# amp_soha.net
KiCad netlist of a schematic drawn in EAGLE
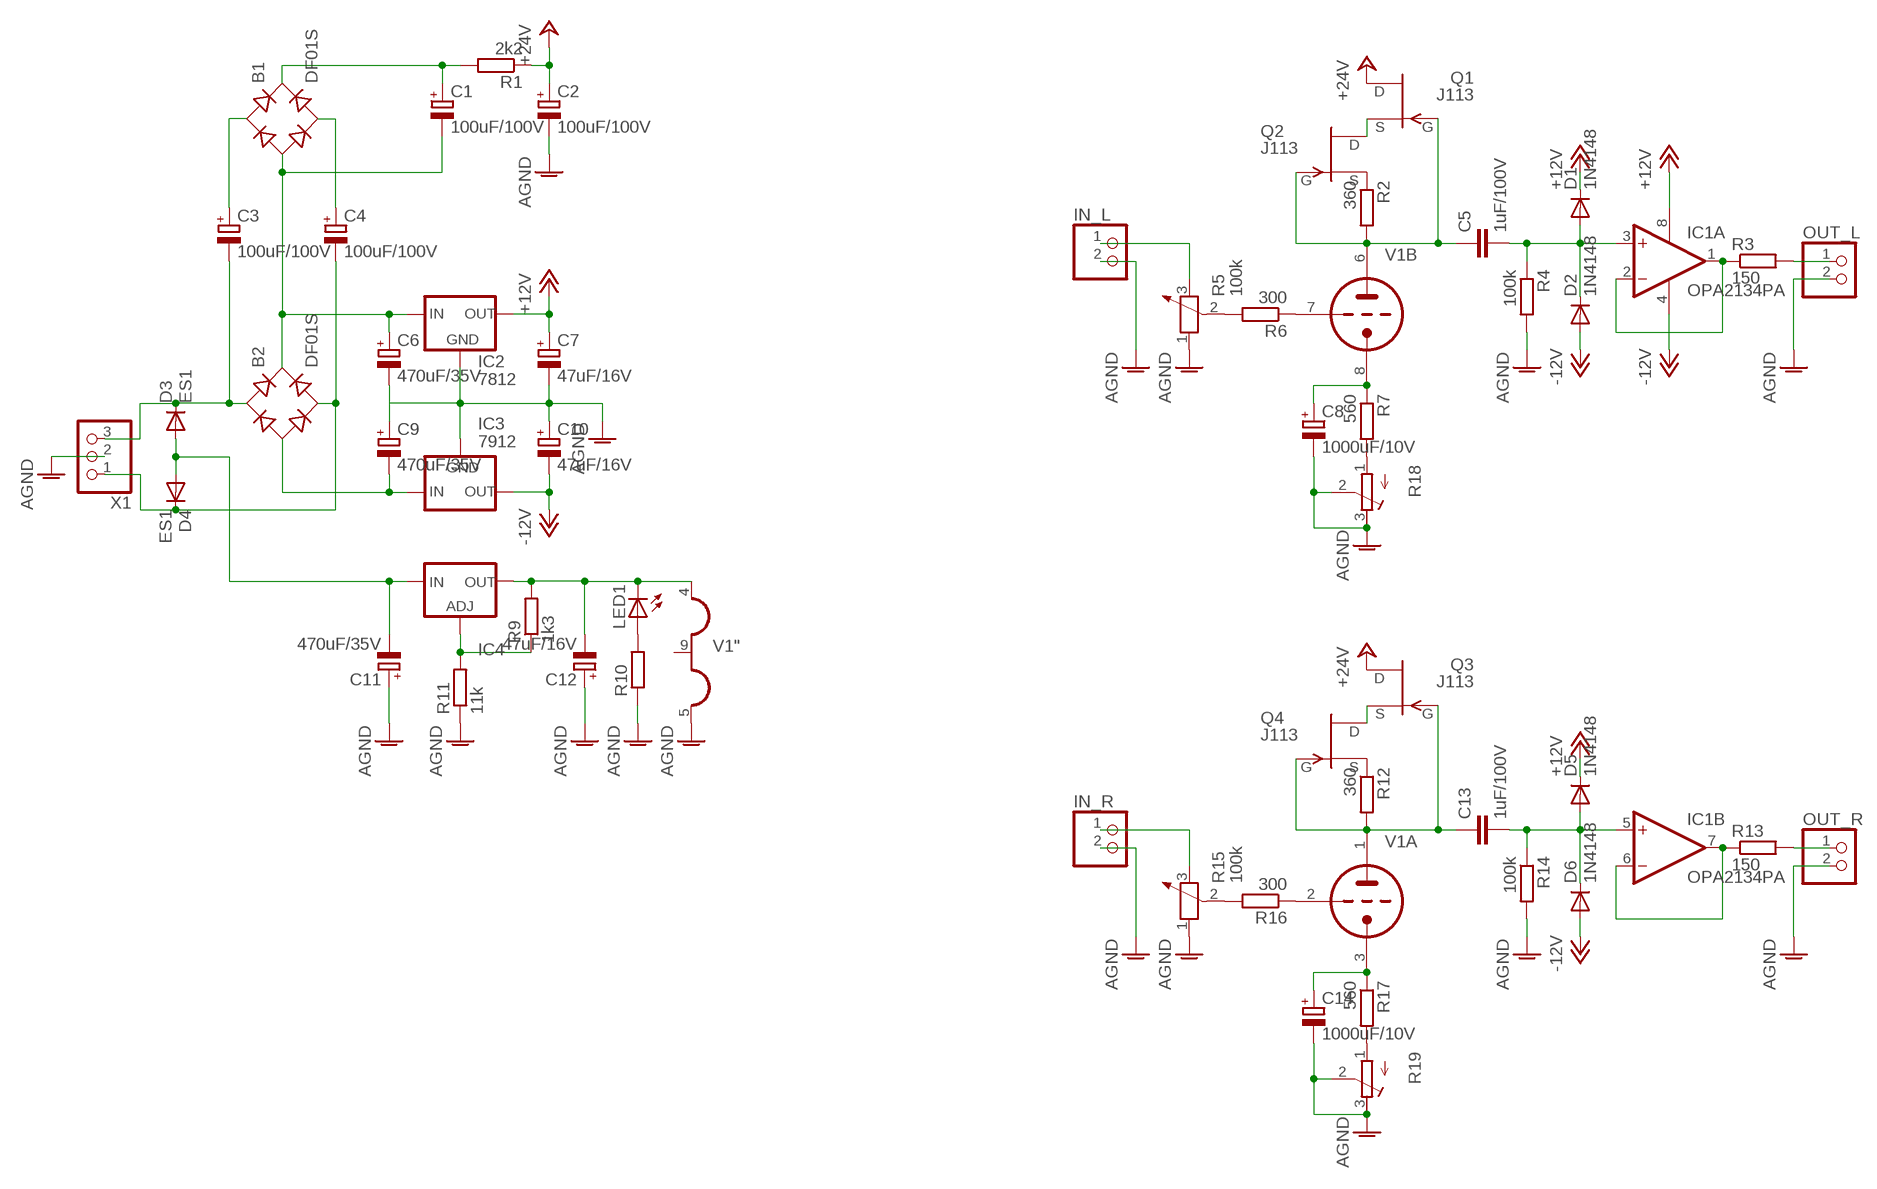
[diagram p0: schematic, sheet 1]

(export (version "E")
  (design (tool "Eeschema 10.0.6"))
  (components
    (comp (ref "B1")
      (value "DF01S")
      (footprint "eagle-import:DFS")
      (libsource (lib "eagle-import") (part "DFS01"))
    )
    (comp (ref "B2")
      (value "DF01S")
      (footprint "eagle-import:DFS")
      (libsource (lib "eagle-import") (part "DFS01"))
    )
    (comp (ref "C1")
      (value "100uF/100V")
      (footprint "eagle-import:E5-10,5")
      (libsource (lib "eagle-import") (part "CPOL-EUE5-10,5"))
    )
    (comp (ref "C2")
      (value "100uF/100V")
      (footprint "eagle-import:E5-10,5")
      (libsource (lib "eagle-import") (part "CPOL-EUE5-10,5"))
    )
    (comp (ref "C3")
      (value "100uF/100V")
      (footprint "eagle-import:E5-10,5")
      (libsource (lib "eagle-import") (part "CPOL-EUE5-10,5"))
    )
    (comp (ref "C4")
      (value "100uF/100V")
      (footprint "eagle-import:E5-10,5")
      (libsource (lib "eagle-import") (part "CPOL-EUE5-10,5"))
    )
    (comp (ref "C5")
      (value "1uF/100V")
      (footprint "eagle-import:C150-072X183")
      (libsource (lib "eagle-import") (part "C-EU150-072X183"))
    )
    (comp (ref "C6")
      (value "470uF/35V")
      (footprint "eagle-import:E5-10,5")
      (libsource (lib "eagle-import") (part "CPOL-EUE5-10,5"))
    )
    (comp (ref "C7")
      (value "47uF/16V")
      (footprint "eagle-import:E2,5-6")
      (libsource (lib "eagle-import") (part "CPOL-EUE2.5-6"))
    )
    (comp (ref "C8")
      (value "1000uF/10V")
      (footprint "eagle-import:E5-10,5")
      (libsource (lib "eagle-import") (part "CPOL-EUE5-10,5"))
    )
    (comp (ref "C9")
      (value "470uF/35V")
      (footprint "eagle-import:E5-10,5")
      (libsource (lib "eagle-import") (part "CPOL-EUE5-10,5"))
    )
    (comp (ref "C10")
      (value "47uF/16V")
      (footprint "eagle-import:E2,5-6")
      (libsource (lib "eagle-import") (part "CPOL-EUE2.5-6"))
    )
    (comp (ref "C11")
      (value "470uF/35V")
      (footprint "eagle-import:E5-10,5")
      (libsource (lib "eagle-import") (part "CPOL-EUE5-10,5"))
    )
    (comp (ref "C12")
      (value "47uF/16V")
      (footprint "eagle-import:E2,5-6")
      (libsource (lib "eagle-import") (part "CPOL-EUE2.5-6"))
    )
    (comp (ref "C13")
      (value "1uF/100V")
      (footprint "eagle-import:C150-072X183")
      (libsource (lib "eagle-import") (part "C-EU150-072X183"))
    )
    (comp (ref "C14")
      (value "1000uF/10V")
      (footprint "eagle-import:E5-10,5")
      (libsource (lib "eagle-import") (part "CPOL-EUE5-10,5"))
    )
    (comp (ref "D1")
      (value "1N4148")
      (footprint "eagle-import:D0805")
      (libsource (lib "eagle-import") (part "1N4148"))
    )
    (comp (ref "D2")
      (value "1N4148")
      (footprint "eagle-import:D0805")
      (libsource (lib "eagle-import") (part "1N4148"))
    )
    (comp (ref "D3")
      (value "ES1")
      (footprint "eagle-import:DO-214AC")
      (libsource (lib "eagle-import") (part "ES1"))
    )
    (comp (ref "D4")
      (value "ES1")
      (footprint "eagle-import:DO-214AC")
      (libsource (lib "eagle-import") (part "ES1"))
    )
    (comp (ref "D5")
      (value "1N4148")
      (footprint "eagle-import:D0805")
      (libsource (lib "eagle-import") (part "1N4148"))
    )
    (comp (ref "D6")
      (value "1N4148")
      (footprint "eagle-import:D0805")
      (libsource (lib "eagle-import") (part "1N4148"))
    )
    (comp (ref "IC1")
      (value "OPA2134PA")
      (footprint "eagle-import:DIL08")
      (libsource (lib "eagle-import") (part "OPA2PA134"))
    )
    (comp (ref "IC2")
      (value "7812")
      (footprint "eagle-import:78XXS")
      (libsource (lib "eagle-import") (part "78XXTO-220"))
    )
    (comp (ref "IC3")
      (value "7912")
      (footprint "eagle-import:79XXS")
      (libsource (lib "eagle-import") (part "79XXTO-220"))
    )
    (comp (ref "IC4")
      (value "LM337TS")
      (footprint "eagle-import:337TS")
      (libsource (lib "eagle-import") (part "LM337TS"))
    )
    (comp (ref "IN_L")
      (value "PINHD-1X2")
      (footprint "eagle-import:1X02")
      (libsource (lib "eagle-import") (part "PINHD-1X2"))
    )
    (comp (ref "IN_R")
      (value "PINHD-1X2")
      (footprint "eagle-import:1X02")
      (libsource (lib "eagle-import") (part "PINHD-1X2"))
    )
    (comp (ref "LED1")
      (value "LED5MM")
      (footprint "eagle-import:LED5MM")
      (libsource (lib "eagle-import") (part "LED5MM"))
    )
    (comp (ref "OUT_L")
      (value "PINHD-1X2")
      (footprint "eagle-import:1X02")
      (libsource (lib "eagle-import") (part "PINHD-1X2"))
    )
    (comp (ref "OUT_R")
      (value "PINHD-1X2")
      (footprint "eagle-import:1X02")
      (libsource (lib "eagle-import") (part "PINHD-1X2"))
    )
    (comp (ref "Q1")
      (value "J113")
      (footprint "eagle-import:TO92")
      (libsource (lib "eagle-import") (part "J113"))
    )
    (comp (ref "Q2")
      (value "J113")
      (footprint "eagle-import:TO92")
      (libsource (lib "eagle-import") (part "J113"))
    )
    (comp (ref "Q3")
      (value "J113")
      (footprint "eagle-import:TO92")
      (libsource (lib "eagle-import") (part "J113"))
    )
    (comp (ref "Q4")
      (value "J113")
      (footprint "eagle-import:TO92")
      (libsource (lib "eagle-import") (part "J113"))
    )
    (comp (ref "R1")
      (value "2k2")
      (footprint "eagle-import:R0805")
      (libsource (lib "eagle-import") (part "R-EU_"))
    )
    (comp (ref "R2")
      (value "360")
      (footprint "eagle-import:R0805")
      (libsource (lib "eagle-import") (part "R-EU_"))
    )
    (comp (ref "R3")
      (value "150")
      (footprint "eagle-import:R0805")
      (libsource (lib "eagle-import") (part "R-EU_"))
    )
    (comp (ref "R4")
      (value "100k")
      (footprint "eagle-import:R0805")
      (libsource (lib "eagle-import") (part "R-EU_"))
    )
    (comp (ref "R5")
      (value "100k")
      (footprint "eagle-import:1X03")
      (libsource (lib "eagle-import") (part "POTENTIOMETER_"))
    )
    (comp (ref "R6")
      (value "300")
      (footprint "eagle-import:R0805")
      (libsource (lib "eagle-import") (part "R-EU_"))
    )
    (comp (ref "R7")
      (value "560")
      (footprint "eagle-import:R0805")
      (libsource (lib "eagle-import") (part "R-EU_"))
    )
    (comp (ref "R9")
      (value "1k3")
      (footprint "eagle-import:R0805")
      (libsource (lib "eagle-import") (part "R-EU_"))
    )
    (comp (ref "R10")
      (value "R-EU_")
      (footprint "eagle-import:R0805")
      (libsource (lib "eagle-import") (part "R-EU_"))
    )
    (comp (ref "R11")
      (value "11k")
      (footprint "eagle-import:R0805")
      (libsource (lib "eagle-import") (part "R-EU_"))
    )
    (comp (ref "R12")
      (value "360")
      (footprint "eagle-import:R0805")
      (libsource (lib "eagle-import") (part "R-EU_"))
    )
    (comp (ref "R13")
      (value "150")
      (footprint "eagle-import:R0805")
      (libsource (lib "eagle-import") (part "R-EU_"))
    )
    (comp (ref "R14")
      (value "100k")
      (footprint "eagle-import:R0805")
      (libsource (lib "eagle-import") (part "R-EU_"))
    )
    (comp (ref "R15")
      (value "100k")
      (footprint "eagle-import:1X03")
      (libsource (lib "eagle-import") (part "POTENTIOMETER_"))
    )
    (comp (ref "R16")
      (value "300")
      (footprint "eagle-import:R0805")
      (libsource (lib "eagle-import") (part "R-EU_"))
    )
    (comp (ref "R17")
      (value "560")
      (footprint "eagle-import:R0805")
      (libsource (lib "eagle-import") (part "R-EU_"))
    )
    (comp (ref "R18")
      (value "RTRIM329Y")
      (footprint "eagle-import:RTRIM3296Y")
      (libsource (lib "eagle-import") (part "RTRIM329Y"))
    )
    (comp (ref "R19")
      (value "RTRIM329Y")
      (footprint "eagle-import:RTRIM3296Y")
      (libsource (lib "eagle-import") (part "RTRIM329Y"))
    )
    (comp (ref "V1")
      (value "12AU7-P")
      (footprint "eagle-import:NOVAL")
      (libsource (lib "eagle-import") (part "12AU7-P"))
    )
    (comp (ref "X1")
      (value "W237-103")
      (footprint "eagle-import:W237-103")
      (libsource (lib "eagle-import") (part "W237-103"))
    )
  )
  (nets
    (net (code "1") (name "+12V") (class "Default")
      (node (ref "C7") (pin "+") (pinfunction "+_+") (pintype "passive"))
      (node (ref "D1") (pin "K") (pinfunction "C_K") (pintype "passive"))
      (node (ref "D5") (pin "K") (pinfunction "C_K") (pintype "passive"))
      (node (ref "IC1") (pin "8") (pinfunction "V+_8") (pintype "power_in"))
      (node (ref "IC2") (pin "OUT") (pinfunction "OUT_OUT") (pintype "passive"))
    )
    (net (code "2") (name "+24V") (class "Default")
      (node (ref "C2") (pin "+") (pinfunction "+_+") (pintype "passive"))
      (node (ref "Q1") (pin "3") (pinfunction "D_3") (pintype "passive"))
      (node (ref "Q3") (pin "3") (pinfunction "D_3") (pintype "passive"))
      (node (ref "R1") (pin "1") (pinfunction "1_1") (pintype "passive"))
    )
    (net (code "3") (name "-12V") (class "Default")
      (node (ref "C10") (pin "-") (pinfunction "-_-") (pintype "passive"))
      (node (ref "D2") (pin "A") (pinfunction "A_A") (pintype "passive"))
      (node (ref "D6") (pin "A") (pinfunction "A_A") (pintype "passive"))
      (node (ref "IC1") (pin "4") (pinfunction "V-_4") (pintype "power_in"))
      (node (ref "IC3") (pin "OUT") (pinfunction "OUT_OUT") (pintype "passive"))
    )
    (net (code "4") (name "AGND") (class "Default")
      (node (ref "C10") (pin "+") (pinfunction "+_+") (pintype "passive"))
      (node (ref "C11") (pin "+") (pinfunction "+_+") (pintype "passive"))
      (node (ref "C12") (pin "+") (pinfunction "+_+") (pintype "passive"))
      (node (ref "C14") (pin "-") (pinfunction "-_-") (pintype "passive"))
      (node (ref "C2") (pin "-") (pinfunction "-_-") (pintype "passive"))
      (node (ref "C6") (pin "-") (pinfunction "-_-") (pintype "passive"))
      (node (ref "C7") (pin "-") (pinfunction "-_-") (pintype "passive"))
      (node (ref "C8") (pin "-") (pinfunction "-_-") (pintype "passive"))
      (node (ref "C9") (pin "+") (pinfunction "+_+") (pintype "passive"))
      (node (ref "IC2") (pin "GND") (pinfunction "GND_GND") (pintype "input"))
      (node (ref "IC3") (pin "GND") (pinfunction "GND_GND") (pintype "input"))
      (node (ref "IN_L") (pin "2") (pinfunction "2_2") (pintype "passive"))
      (node (ref "IN_R") (pin "2") (pinfunction "2_2") (pintype "passive"))
      (node (ref "OUT_L") (pin "2") (pinfunction "2_2") (pintype "passive"))
      (node (ref "OUT_R") (pin "2") (pinfunction "2_2") (pintype "passive"))
      (node (ref "R10") (pin "1") (pinfunction "1_1") (pintype "passive"))
      (node (ref "R11") (pin "1") (pinfunction "1_1") (pintype "passive"))
      (node (ref "R14") (pin "2") (pinfunction "2_2") (pintype "passive"))
      (node (ref "R15") (pin "1") (pinfunction "1_1") (pintype "passive"))
      (node (ref "R18") (pin "2") (pinfunction "S_2") (pintype "passive"))
      (node (ref "R18") (pin "3") (pinfunction "E_3") (pintype "passive"))
      (node (ref "R19") (pin "2") (pinfunction "S_2") (pintype "passive"))
      (node (ref "R19") (pin "3") (pinfunction "E_3") (pintype "passive"))
      (node (ref "R4") (pin "2") (pinfunction "2_2") (pintype "passive"))
      (node (ref "R5") (pin "1") (pinfunction "1_1") (pintype "passive"))
      (node (ref "V1") (pin "5") (pinfunction "H3_5") (pintype "passive"))
      (node (ref "X1") (pin "2") (pinfunction "2_2") (pintype "passive"))
    )
    (net (code "5") (name "Net-(B1-Pad+)") (class "Default")
      (node (ref "B1") (pin "+") (pinfunction "+_+") (pintype "passive"))
      (node (ref "C1") (pin "+") (pinfunction "+_+") (pintype "passive"))
      (node (ref "R1") (pin "2") (pinfunction "2_2") (pintype "passive"))
    )
    (net (code "6") (name "Net-(B1-Pad-)") (class "Default")
      (node (ref "B1") (pin "-") (pinfunction "-_-") (pintype "passive"))
      (node (ref "B2") (pin "+") (pinfunction "+_+") (pintype "passive"))
      (node (ref "C1") (pin "-") (pinfunction "-_-") (pintype "passive"))
      (node (ref "C6") (pin "+") (pinfunction "+_+") (pintype "passive"))
      (node (ref "IC2") (pin "IN") (pinfunction "IN_IN") (pintype "input"))
    )
    (net (code "7") (name "Net-(B1-PadAC1)") (class "Default")
      (node (ref "B1") (pin "AC1") (pinfunction "AC1_AC1") (pintype "passive"))
      (node (ref "C3") (pin "+") (pinfunction "+_+") (pintype "passive"))
    )
    (net (code "8") (name "Net-(B1-PadAC2)") (class "Default")
      (node (ref "B1") (pin "AC2") (pinfunction "AC2_AC2") (pintype "passive"))
      (node (ref "C4") (pin "+") (pinfunction "+_+") (pintype "passive"))
    )
    (net (code "9") (name "Net-(B2-Pad-)") (class "Default")
      (node (ref "B2") (pin "-") (pinfunction "-_-") (pintype "passive"))
      (node (ref "C9") (pin "-") (pinfunction "-_-") (pintype "passive"))
      (node (ref "IC3") (pin "IN") (pinfunction "IN_IN") (pintype "input"))
    )
    (net (code "10") (name "Net-(B2-PadAC1)") (class "Default")
      (node (ref "B2") (pin "AC1") (pinfunction "AC1_AC1") (pintype "passive"))
      (node (ref "C3") (pin "-") (pinfunction "-_-") (pintype "passive"))
      (node (ref "D3") (pin "C") (pinfunction "C_C") (pintype "passive"))
      (node (ref "X1") (pin "3") (pinfunction "3_3") (pintype "passive"))
    )
    (net (code "11") (name "Net-(B2-PadAC2)") (class "Default")
      (node (ref "B2") (pin "AC2") (pinfunction "AC2_AC2") (pintype "passive"))
      (node (ref "C4") (pin "-") (pinfunction "-_-") (pintype "passive"))
      (node (ref "D4") (pin "C") (pinfunction "C_C") (pintype "passive"))
      (node (ref "X1") (pin "1") (pinfunction "1_1") (pintype "passive"))
    )
    (net (code "12") (name "Net-(D2-C)") (class "Default")
      (node (ref "C5") (pin "2") (pinfunction "2_2") (pintype "passive"))
      (node (ref "D1") (pin "A") (pinfunction "A_A") (pintype "passive"))
      (node (ref "D2") (pin "K") (pinfunction "C_K") (pintype "passive"))
      (node (ref "IC1") (pin "3") (pinfunction "+IN_3") (pintype "input"))
      (node (ref "R4") (pin "1") (pinfunction "1_1") (pintype "passive"))
    )
    (net (code "13") (name "Net-(D6-C)") (class "Default")
      (node (ref "C13") (pin "2") (pinfunction "2_2") (pintype "passive"))
      (node (ref "D5") (pin "A") (pinfunction "A_A") (pintype "passive"))
      (node (ref "D6") (pin "K") (pinfunction "C_K") (pintype "passive"))
      (node (ref "IC1") (pin "5") (pinfunction "+IN_5") (pintype "input"))
      (node (ref "R14") (pin "1") (pinfunction "1_1") (pintype "passive"))
    )
    (net (code "14") (name "Net-(IC1A--IN)") (class "Default")
      (node (ref "IC1") (pin "1") (pinfunction "OUT_1") (pintype "output"))
      (node (ref "IC1") (pin "2") (pinfunction "-IN_2") (pintype "input"))
      (node (ref "R3") (pin "1") (pinfunction "1_1") (pintype "passive"))
    )
    (net (code "15") (name "Net-(IC1B--IN)") (class "Default")
      (node (ref "IC1") (pin "6") (pinfunction "-IN_6") (pintype "input"))
      (node (ref "IC1") (pin "7") (pinfunction "OUT_7") (pintype "output"))
      (node (ref "R13") (pin "1") (pinfunction "1_1") (pintype "passive"))
    )
    (net (code "16") (name "Net-(IC4-ADJ)") (class "Default")
      (node (ref "IC4") (pin "1") (pinfunction "ADJ_1") (pintype "input"))
      (node (ref "R11") (pin "2") (pinfunction "2_2") (pintype "passive"))
      (node (ref "R9") (pin "1") (pinfunction "1_1") (pintype "passive"))
    )
    (net (code "17") (name "Net-(IC4-IN)") (class "Default")
      (node (ref "C11") (pin "-") (pinfunction "-_-") (pintype "passive"))
      (node (ref "D3") (pin "A") (pinfunction "A_A") (pintype "passive"))
      (node (ref "D4") (pin "A") (pinfunction "A_A") (pintype "passive"))
      (node (ref "IC4") (pin "2") (pinfunction "IN_2") (pintype "input"))
    )
    (net (code "18") (name "Net-(IC4-OUT)") (class "Default")
      (node (ref "C12") (pin "-") (pinfunction "-_-") (pintype "passive"))
      (node (ref "IC4") (pin "3") (pinfunction "OUT_3") (pintype "passive"))
      (node (ref "LED1") (pin "K") (pinfunction "C_K") (pintype "passive"))
      (node (ref "R9") (pin "2") (pinfunction "2_2") (pintype "passive"))
      (node (ref "V1") (pin "4") (pinfunction "H1_4") (pintype "passive"))
    )
    (net (code "19") (name "Net-(LED1-PadA)") (class "Default")
      (node (ref "LED1") (pin "A") (pinfunction "A_A") (pintype "passive"))
      (node (ref "R10") (pin "2") (pinfunction "2_2") (pintype "passive"))
    )
    (net (code "20") (name "Net-(OUT_L-Pad1)") (class "Default")
      (node (ref "OUT_L") (pin "1") (pinfunction "1_1") (pintype "passive"))
      (node (ref "R3") (pin "2") (pinfunction "2_2") (pintype "passive"))
    )
    (net (code "21") (name "Net-(OUT_R-Pad1)") (class "Default")
      (node (ref "OUT_R") (pin "1") (pinfunction "1_1") (pintype "passive"))
      (node (ref "R13") (pin "2") (pinfunction "2_2") (pintype "passive"))
    )
    (net (code "22") (name "Net-(Q1-G)") (class "Default")
      (node (ref "C5") (pin "1") (pinfunction "1_1") (pintype "passive"))
      (node (ref "Q1") (pin "1") (pinfunction "G_1") (pintype "passive"))
      (node (ref "Q2") (pin "1") (pinfunction "G_1") (pintype "passive"))
      (node (ref "R2") (pin "2") (pinfunction "2_2") (pintype "passive"))
      (node (ref "V1") (pin "6") (pinfunction "TA_6") (pintype "passive"))
    )
    (net (code "23") (name "Net-(Q1-S)") (class "Default")
      (node (ref "Q1") (pin "2") (pinfunction "S_2") (pintype "passive"))
      (node (ref "Q2") (pin "3") (pinfunction "D_3") (pintype "passive"))
    )
    (net (code "24") (name "Net-(Q2-S)") (class "Default")
      (node (ref "Q2") (pin "2") (pinfunction "S_2") (pintype "passive"))
      (node (ref "R2") (pin "1") (pinfunction "1_1") (pintype "passive"))
    )
    (net (code "25") (name "Net-(Q3-G)") (class "Default")
      (node (ref "C13") (pin "1") (pinfunction "1_1") (pintype "passive"))
      (node (ref "Q3") (pin "1") (pinfunction "G_1") (pintype "passive"))
      (node (ref "Q4") (pin "1") (pinfunction "G_1") (pintype "passive"))
      (node (ref "R12") (pin "2") (pinfunction "2_2") (pintype "passive"))
      (node (ref "V1") (pin "1") (pinfunction "TA_1") (pintype "passive"))
    )
    (net (code "26") (name "Net-(Q3-S)") (class "Default")
      (node (ref "Q3") (pin "2") (pinfunction "S_2") (pintype "passive"))
      (node (ref "Q4") (pin "3") (pinfunction "D_3") (pintype "passive"))
    )
    (net (code "27") (name "Net-(Q4-S)") (class "Default")
      (node (ref "Q4") (pin "2") (pinfunction "S_2") (pintype "passive"))
      (node (ref "R12") (pin "1") (pinfunction "1_1") (pintype "passive"))
    )
    (net (code "28") (name "Net-(R5-2)") (class "Default")
      (node (ref "IN_L") (pin "1") (pinfunction "1_1") (pintype "passive"))
      (node (ref "R5") (pin "3") (pinfunction "2_3") (pintype "passive"))
    )
    (net (code "29") (name "Net-(R5-3)") (class "Default")
      (node (ref "R5") (pin "2") (pinfunction "3_2") (pintype "passive"))
      (node (ref "R6") (pin "2") (pinfunction "2_2") (pintype "passive"))
    )
    (net (code "30") (name "Net-(R15-2)") (class "Default")
      (node (ref "IN_R") (pin "1") (pinfunction "1_1") (pintype "passive"))
      (node (ref "R15") (pin "3") (pinfunction "2_3") (pintype "passive"))
    )
    (net (code "31") (name "Net-(R15-3)") (class "Default")
      (node (ref "R15") (pin "2") (pinfunction "3_2") (pintype "passive"))
      (node (ref "R16") (pin "2") (pinfunction "2_2") (pintype "passive"))
    )
    (net (code "32") (name "Net-(R18-A)") (class "Default")
      (node (ref "R18") (pin "1") (pinfunction "A_1") (pintype "passive"))
      (node (ref "R7") (pin "2") (pinfunction "2_2") (pintype "passive"))
    )
    (net (code "33") (name "Net-(R19-A)") (class "Default")
      (node (ref "R17") (pin "2") (pinfunction "2_2") (pintype "passive"))
      (node (ref "R19") (pin "1") (pinfunction "A_1") (pintype "passive"))
    )
    (net (code "34") (name "Net-(V1B-TG)") (class "Default")
      (node (ref "R16") (pin "1") (pinfunction "1_1") (pintype "passive"))
      (node (ref "V1") (pin "2") (pinfunction "TG_2") (pintype "passive"))
    )
    (net (code "35") (name "Net-(V1B-TK)") (class "Default")
      (node (ref "C14") (pin "+") (pinfunction "+_+") (pintype "passive"))
      (node (ref "R17") (pin "1") (pinfunction "1_1") (pintype "passive"))
      (node (ref "V1") (pin "3") (pinfunction "TK_3") (pintype "passive"))
    )
    (net (code "36") (name "Net-(V1C-TG)") (class "Default")
      (node (ref "R6") (pin "1") (pinfunction "1_1") (pintype "passive"))
      (node (ref "V1") (pin "7") (pinfunction "TG_7") (pintype "passive"))
    )
    (net (code "37") (name "Net-(V1C-TK)") (class "Default")
      (node (ref "C8") (pin "+") (pinfunction "+_+") (pintype "passive"))
      (node (ref "R7") (pin "1") (pinfunction "1_1") (pintype "passive"))
      (node (ref "V1") (pin "8") (pinfunction "TK_8") (pintype "passive"))
    )
    (net (code "38") (name "unconnected-(V1A-H2-Pad9)") (class "Default")
      (node (ref "V1") (pin "9") (pinfunction "H2_9") (pintype "passive"))
    )
  )
)
